# board.net
KiCad netlist of a schematic drawn in EAGLE
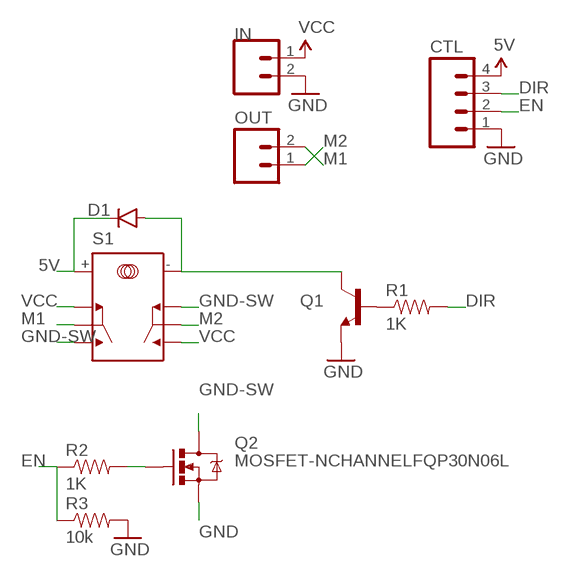
[diagram p0: schematic, sheet 1]

(export (version "E")
  (design (tool "Eeschema 10.0.6"))
  (components
    (comp (ref "CTL")
      (value "M041X04_NO_SILK")
      (footprint "eagle-import:1X04_NO_SILK")
      (libsource (lib "eagle-import") (part "M041X04_NO_SILK"))
    )
    (comp (ref "D1")
      (value "DIODE1N4148")
      (footprint "eagle-import:DIODE-1N4148")
      (libsource (lib "eagle-import") (part "DIODE1N4148"))
    )
    (comp (ref "IN")
      (value "M023.5MM")
      (footprint "eagle-import:SCREWTERMINAL-3.5MM-2")
      (libsource (lib "eagle-import") (part "M023.5MM"))
    )
    (comp (ref "OUT")
      (value "M023.5MM")
      (footprint "eagle-import:SCREWTERMINAL-3.5MM-2")
      (libsource (lib "eagle-import") (part "M023.5MM"))
    )
    (comp (ref "Q1")
      (value "TRANSISTOR_NPNTO-92-AMMO")
      (footprint "eagle-import:TO-92-AMMO")
      (libsource (lib "eagle-import") (part "TRANSISTOR_NPNTO-92-AMMO"))
    )
    (comp (ref "Q2")
      (value "MOSFET-NCHANNELFQP30N06L")
      (footprint "eagle-import:TO220V")
      (libsource (lib "eagle-import") (part "MOSFET-NCHANNELFQP30N06L"))
    )
    (comp (ref "R1")
      (value "1K")
      (footprint "eagle-import:AXIAL-0.3")
      (libsource (lib "eagle-import") (part "1KOHM-1/4W-1%(PTH)"))
    )
    (comp (ref "R2")
      (value "1K")
      (footprint "eagle-import:AXIAL-0.3")
      (libsource (lib "eagle-import") (part "1KOHM-1/4W-1%(PTH)"))
    )
    (comp (ref "R3")
      (value "10k")
      (footprint "eagle-import:AXIAL-0.3")
      (libsource (lib "eagle-import") (part "10KOHM-1/4W-1%(PTH)HORIZ"))
    )
    (comp (ref "S1")
      (value "EC2-5NU")
      (footprint "eagle-import:EC2-5NU")
      (libsource (lib "eagle-import") (part "EC2-5NU"))
    )
  )
  (nets
    (net (code "1") (name "/DIR") (class "Default")
      (node (ref "CTL") (pin "3") (pinfunction "3_3") (pintype "passive"))
      (node (ref "R1") (pin "P$2") (pinfunction "2_P$2") (pintype "passive"))
    )
    (net (code "2") (name "/EN") (class "Default")
      (node (ref "CTL") (pin "2") (pinfunction "2_2") (pintype "passive"))
      (node (ref "R2") (pin "P$1") (pinfunction "1_P$1") (pintype "passive"))
      (node (ref "R3") (pin "P$1") (pinfunction "1_P$1") (pintype "passive"))
    )
    (net (code "3") (name "/GND-SW") (class "Default")
      (node (ref "Q2") (pin "2") (pinfunction "D_2") (pintype "passive"))
      (node (ref "S1") (pin "NC2") (pinfunction "NC2_NC2") (pintype "bidirectional"))
      (node (ref "S1") (pin "NO1") (pinfunction "NO1_NO1") (pintype "bidirectional"))
    )
    (net (code "4") (name "/M1") (class "Default")
      (node (ref "OUT") (pin "2") (pinfunction "2_2") (pintype "passive"))
      (node (ref "S1") (pin "COM1") (pinfunction "COM1_COM1") (pintype "bidirectional"))
    )
    (net (code "5") (name "/M2") (class "Default")
      (node (ref "OUT") (pin "1") (pinfunction "1_1") (pintype "passive"))
      (node (ref "S1") (pin "COM2") (pinfunction "COM2_COM2") (pintype "bidirectional"))
    )
    (net (code "6") (name "5V") (class "Default")
      (node (ref "CTL") (pin "4") (pinfunction "4_4") (pintype "passive"))
      (node (ref "D1") (pin "C") (pinfunction "C_C") (pintype "passive"))
      (node (ref "S1") (pin "+") (pinfunction "+_+") (pintype "power_in"))
    )
    (net (code "7") (name "GND") (class "Default")
      (node (ref "CTL") (pin "1") (pinfunction "1_1") (pintype "passive"))
      (node (ref "IN") (pin "2") (pinfunction "2_2") (pintype "passive"))
      (node (ref "Q1") (pin "1") (pinfunction "E_1") (pintype "passive"))
      (node (ref "Q2") (pin "3") (pinfunction "S_3") (pintype "passive"))
      (node (ref "R3") (pin "P$2") (pinfunction "2_P$2") (pintype "passive"))
    )
    (net (code "8") (name "Net-(Q1-B)") (class "Default")
      (node (ref "Q1") (pin "2") (pinfunction "B_2") (pintype "passive"))
      (node (ref "R1") (pin "P$1") (pinfunction "1_P$1") (pintype "passive"))
    )
    (net (code "9") (name "Net-(Q1-C)") (class "Default")
      (node (ref "D1") (pin "A") (pinfunction "A_A") (pintype "passive"))
      (node (ref "Q1") (pin "3") (pinfunction "C_3") (pintype "passive"))
      (node (ref "S1") (pin "-") (pinfunction "-_-") (pintype "power_in"))
    )
    (net (code "10") (name "Net-(Q2-G)") (class "Default")
      (node (ref "Q2") (pin "1") (pinfunction "G_1") (pintype "passive"))
      (node (ref "R2") (pin "P$2") (pinfunction "2_P$2") (pintype "passive"))
    )
    (net (code "11") (name "VCC") (class "Default")
      (node (ref "IN") (pin "1") (pinfunction "1_1") (pintype "passive"))
      (node (ref "S1") (pin "NC1") (pinfunction "NC1_NC1") (pintype "bidirectional"))
      (node (ref "S1") (pin "NO2") (pinfunction "NO2_NO2") (pintype "bidirectional"))
    )
  )
)
